# MOTOR.net
KiCad netlist of a schematic drawn in Altium Designer
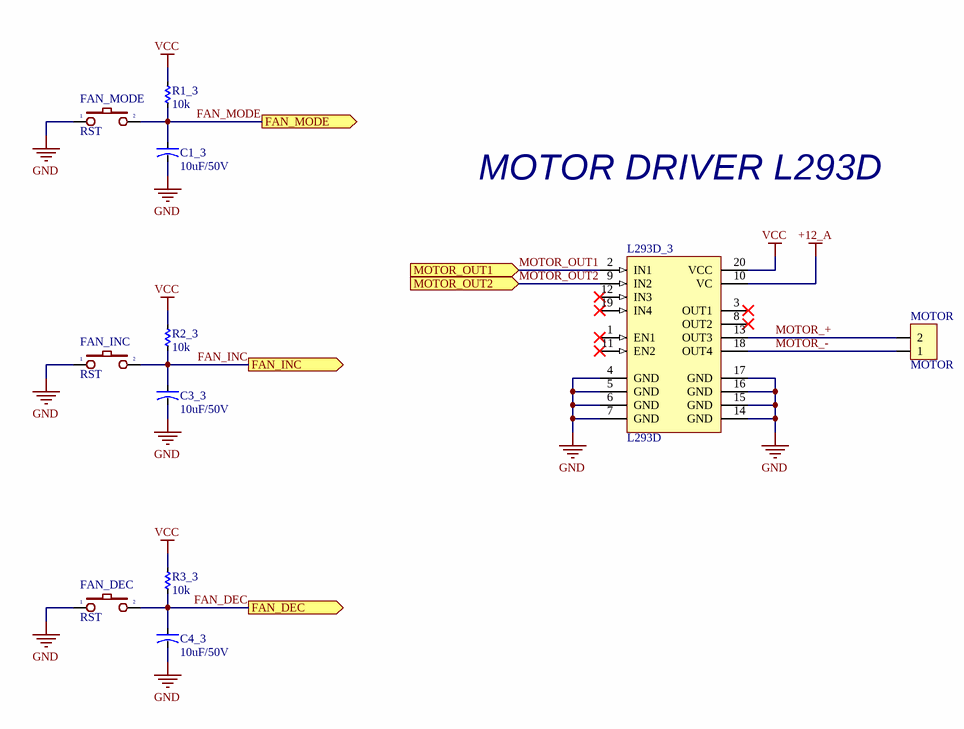
[diagram p0: MOTOR.SchDoc]

(export (version "E")
  (design (tool "Eeschema 10.0.6"))
  (components
    (comp (ref "C1_3")
      (value "10uF/50V")
      (footprint "CAP-ALU-SMD-5.5x5.5")
      (description "Polarized Capacitor (Axial)")
      (fields (field (name "PUBLISHER") "Altium Limited"))
      (libsource (lib "Altium Library") (part "CN-ALU-SMD"))
    )
    (comp (ref "C3_3")
      (value "10uF/50V")
      (footprint "CAP-ALU-SMD-5.5x5.5")
      (description "Polarized Capacitor (Axial)")
      (fields (field (name "PUBLISHER") "Altium Limited"))
      (libsource (lib "Altium Library") (part "CN-ALU-SMD"))
    )
    (comp (ref "C4_3")
      (value "10uF/50V")
      (footprint "CAP-ALU-SMD-5.5x5.5")
      (description "Polarized Capacitor (Axial)")
      (fields (field (name "PUBLISHER") "Altium Limited"))
      (libsource (lib "Altium Library") (part "CN-ALU-SMD"))
    )
    (comp (ref "FAN_DEC")
      (value "RST")
      (footprint "SW1-SMD")
      (description "Switch button 2 pin")
      (libsource (lib "Altium Library") (part "SW2"))
    )
    (comp (ref "FAN_INC")
      (value "RST")
      (footprint "SW1-SMD")
      (description "Switch button 2 pin")
      (libsource (lib "Altium Library") (part "SW2"))
    )
    (comp (ref "FAN_MODE")
      (value "RST")
      (footprint "SW1-SMD")
      (description "Switch button 2 pin")
      (libsource (lib "Altium Library") (part "SW2"))
    )
    (comp (ref "L293D_3")
      (value "L293D")
      (footprint "SO20")
      (description "Push-Pull Four Channel Driver With Diode")
      (fields (field (name "PUBLISHER") "Altium Limited"))
      (libsource (lib "Altium Library") (part "L293D_SMD"))
    )
    (comp (ref "MOTOR")
      (value "MOTOR")
      (footprint "Header2")
      (description "Header IDC, 2 x 1 Pin Vertical 2.54mm Pitch (Non-Boxed, Male)")
      (fields
        (field (name "MANUFACTURER") "Würth Elektronik eiSos GmbH")
        (field (name "PARTNO") "613002143121")
        (field (name "CREATED BY") "Karrer Zheng")
      )
      (libsource (lib "Altium Library") (part "Header2"))
    )
    (comp (ref "R1_3")
      (value "10k")
      (footprint "RES-SMD-0805")
      (description "Resistor")
      (fields
        (field (name "MANUFACTURER") "Generic Components")
        (field (name "PUBLISHER") "Altium Hobart Technology Centre")
      )
      (libsource (lib "Altium Library") (part "Res-SMD"))
    )
    (comp (ref "R2_3")
      (value "10k")
      (footprint "RES-SMD-0805")
      (description "Resistor")
      (fields
        (field (name "MANUFACTURER") "Generic Components")
        (field (name "PUBLISHER") "Altium Hobart Technology Centre")
      )
      (libsource (lib "Altium Library") (part "Res-SMD"))
    )
    (comp (ref "R3_3")
      (value "10k")
      (footprint "RES-SMD-0805")
      (description "Resistor")
      (fields
        (field (name "MANUFACTURER") "Generic Components")
        (field (name "PUBLISHER") "Altium Hobart Technology Centre")
      )
      (libsource (lib "Altium Library") (part "Res-SMD"))
    )
  )
  (nets
    (net (code "1") (name "+12_A") (class "Default")
      (node (ref "L293D_3") (pin "10") (pinfunction "VC_10") (pintype "power_in"))
    )
    (net (code "2") (name "/FAN_DEC") (class "Default")
      (node (ref "C4_3") (pin "1") (pinfunction "1_1") (pintype "passive"))
      (node (ref "FAN_DEC") (pin "2") (pinfunction "2_2") (pintype "passive"))
      (node (ref "R3_3") (pin "2") (pinfunction "2_2") (pintype "passive"))
    )
    (net (code "3") (name "/FAN_INC") (class "Default")
      (node (ref "C3_3") (pin "1") (pinfunction "1_1") (pintype "passive"))
      (node (ref "FAN_INC") (pin "2") (pinfunction "2_2") (pintype "passive"))
      (node (ref "R2_3") (pin "2") (pinfunction "2_2") (pintype "passive"))
    )
    (net (code "4") (name "/FAN_MODE") (class "Default")
      (node (ref "C1_3") (pin "1") (pinfunction "1_1") (pintype "passive"))
      (node (ref "FAN_MODE") (pin "2") (pinfunction "2_2") (pintype "passive"))
      (node (ref "R1_3") (pin "2") (pinfunction "2_2") (pintype "passive"))
    )
    (net (code "5") (name "/MOTOR_+") (class "Default")
      (node (ref "L293D_3") (pin "13") (pinfunction "OUT3_13") (pintype "tri_state"))
      (node (ref "MOTOR") (pin "2") (pinfunction "2_2") (pintype "passive"))
    )
    (net (code "6") (name "/MOTOR_-") (class "Default")
      (node (ref "L293D_3") (pin "18") (pinfunction "OUT4_18") (pintype "tri_state"))
      (node (ref "MOTOR") (pin "1") (pinfunction "1_1") (pintype "passive"))
    )
    (net (code "7") (name "/MOTOR_OUT1") (class "Default")
      (node (ref "L293D_3") (pin "2") (pinfunction "IN1_2") (pintype "input"))
    )
    (net (code "8") (name "/MOTOR_OUT2") (class "Default")
      (node (ref "L293D_3") (pin "9") (pinfunction "IN2_9") (pintype "input"))
    )
    (net (code "9") (name "GND") (class "Default")
      (node (ref "C1_3") (pin "2") (pinfunction "2_2") (pintype "passive"))
      (node (ref "C3_3") (pin "2") (pinfunction "2_2") (pintype "passive"))
      (node (ref "C4_3") (pin "2") (pinfunction "2_2") (pintype "passive"))
      (node (ref "FAN_DEC") (pin "1") (pinfunction "1_1") (pintype "passive"))
      (node (ref "FAN_INC") (pin "1") (pinfunction "1_1") (pintype "passive"))
      (node (ref "FAN_MODE") (pin "1") (pinfunction "1_1") (pintype "passive"))
      (node (ref "L293D_3") (pin "14") (pinfunction "GND_14") (pintype "power_in"))
      (node (ref "L293D_3") (pin "15") (pinfunction "GND_15") (pintype "power_in"))
      (node (ref "L293D_3") (pin "16") (pinfunction "GND_16") (pintype "power_in"))
      (node (ref "L293D_3") (pin "17") (pinfunction "GND_17") (pintype "power_in"))
      (node (ref "L293D_3") (pin "4") (pinfunction "GND_4") (pintype "power_in"))
      (node (ref "L293D_3") (pin "5") (pinfunction "GND_5") (pintype "power_in"))
      (node (ref "L293D_3") (pin "6") (pinfunction "GND_6") (pintype "power_in"))
      (node (ref "L293D_3") (pin "7") (pinfunction "GND_7") (pintype "power_in"))
    )
    (net (code "10") (name "VCC") (class "Default")
      (node (ref "L293D_3") (pin "20") (pinfunction "VCC_20") (pintype "power_in"))
      (node (ref "R1_3") (pin "1") (pinfunction "1_1") (pintype "passive"))
      (node (ref "R2_3") (pin "1") (pinfunction "1_1") (pintype "passive"))
      (node (ref "R3_3") (pin "1") (pinfunction "1_1") (pintype "passive"))
    )
    (net (code "11") (name "unconnected-(L293D_3-EN1-Pad1)") (class "Default")
      (node (ref "L293D_3") (pin "1") (pinfunction "EN1_1") (pintype "input+no_connect"))
    )
    (net (code "12") (name "unconnected-(L293D_3-EN2-Pad11)") (class "Default")
      (node (ref "L293D_3") (pin "11") (pinfunction "EN2_11") (pintype "input+no_connect"))
    )
    (net (code "13") (name "unconnected-(L293D_3-IN3-Pad12)") (class "Default")
      (node (ref "L293D_3") (pin "12") (pinfunction "IN3_12") (pintype "input+no_connect"))
    )
    (net (code "14") (name "unconnected-(L293D_3-IN4-Pad19)") (class "Default")
      (node (ref "L293D_3") (pin "19") (pinfunction "IN4_19") (pintype "input+no_connect"))
    )
    (net (code "15") (name "unconnected-(L293D_3-OUT1-Pad3)") (class "Default")
      (node (ref "L293D_3") (pin "3") (pinfunction "OUT1_3") (pintype "tri_state+no_connect"))
    )
    (net (code "16") (name "unconnected-(L293D_3-OUT2-Pad8)") (class "Default")
      (node (ref "L293D_3") (pin "8") (pinfunction "OUT2_8") (pintype "tri_state+no_connect"))
    )
  )
)
